# clock.net
KiCad netlist of a schematic drawn in EAGLE
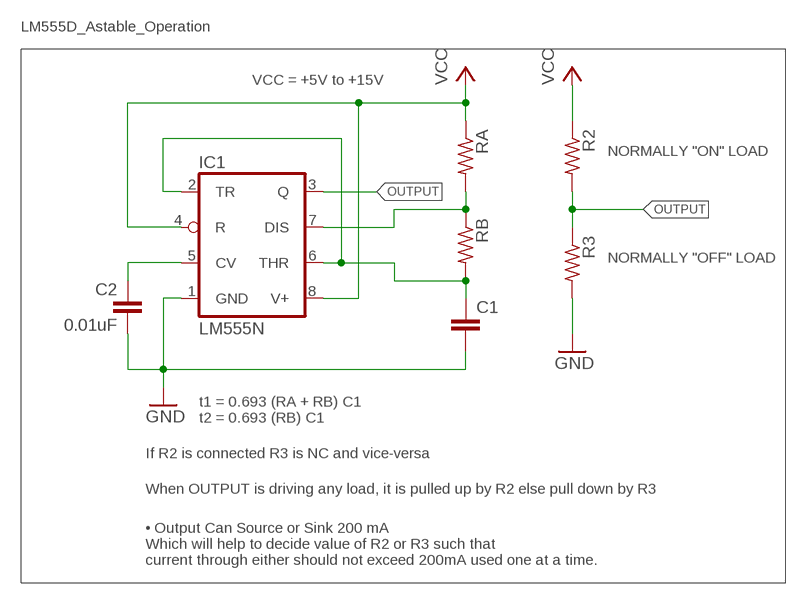
[diagram p0: schematic, sheet 1]

(export (version "E")
  (design (tool "Eeschema 10.0.6"))
  (components
    (comp (ref "C1")
      (value "C-EU025-025X050")
      (footprint "eagle-import:C025-025X050")
      (libsource (lib "eagle-import") (part "C-EU025-025X050"))
    )
    (comp (ref "C2")
      (value "0.01uF")
      (footprint "eagle-import:C025-025X050")
      (libsource (lib "eagle-import") (part "C-EU025-025X050"))
    )
    (comp (ref "IC1")
      (value "LM555N")
      (footprint "eagle-import:DIL08")
      (libsource (lib "eagle-import") (part "555NLM"))
    )
    (comp (ref "R2")
      (value "R-US_R0805")
      (footprint "eagle-import:R0805")
      (libsource (lib "eagle-import") (part "R-US_R0805"))
    )
    (comp (ref "R3")
      (value "R-US_R0805")
      (footprint "eagle-import:R0805")
      (libsource (lib "eagle-import") (part "R-US_R0805"))
    )
    (comp (ref "RA")
      (value "R-US_R0805")
      (footprint "eagle-import:R0805")
      (libsource (lib "eagle-import") (part "R-US_R0805"))
    )
    (comp (ref "RB")
      (value "R-US_R0805")
      (footprint "eagle-import:R0805")
      (libsource (lib "eagle-import") (part "R-US_R0805"))
    )
  )
  (nets
    (net (code "1") (name "GND") (class "Default")
      (node (ref "C1") (pin "2") (pinfunction "2_2") (pintype "passive"))
      (node (ref "C2") (pin "2") (pinfunction "2_2") (pintype "passive"))
      (node (ref "IC1") (pin "1") (pinfunction "GND_1") (pintype "power_in"))
      (node (ref "R3") (pin "2") (pinfunction "2_2") (pintype "passive"))
    )
    (net (code "2") (name "Net-(IC1-CV)") (class "Default")
      (node (ref "C2") (pin "1") (pinfunction "1_1") (pintype "passive"))
      (node (ref "IC1") (pin "5") (pinfunction "CV_5") (pintype "input"))
    )
    (net (code "3") (name "Net-(IC1-DIS)") (class "Default")
      (node (ref "IC1") (pin "7") (pinfunction "DIS_7") (pintype "input"))
      (node (ref "RA") (pin "2") (pinfunction "2_2") (pintype "passive"))
      (node (ref "RB") (pin "1") (pinfunction "1_1") (pintype "passive"))
    )
    (net (code "4") (name "Net-(IC1-THR)") (class "Default")
      (node (ref "C1") (pin "1") (pinfunction "1_1") (pintype "passive"))
      (node (ref "IC1") (pin "2") (pinfunction "TR_2") (pintype "input"))
      (node (ref "IC1") (pin "6") (pinfunction "THR_6") (pintype "input"))
      (node (ref "RB") (pin "2") (pinfunction "2_2") (pintype "passive"))
    )
    (net (code "5") (name "OUTPUT") (class "Default")
      (node (ref "IC1") (pin "3") (pinfunction "Q_3") (pintype "output"))
      (node (ref "R2") (pin "2") (pinfunction "2_2") (pintype "passive"))
      (node (ref "R3") (pin "1") (pinfunction "1_1") (pintype "passive"))
    )
    (net (code "6") (name "VCC") (class "Default")
      (node (ref "IC1") (pin "4") (pinfunction "R_4") (pintype "input"))
      (node (ref "IC1") (pin "8") (pinfunction "V+_8") (pintype "power_in"))
      (node (ref "R2") (pin "1") (pinfunction "1_1") (pintype "passive"))
      (node (ref "RA") (pin "1") (pinfunction "1_1") (pintype "passive"))
    )
  )
)
